# carDoor.net
KiCad netlist of a schematic drawn in Altium Designer
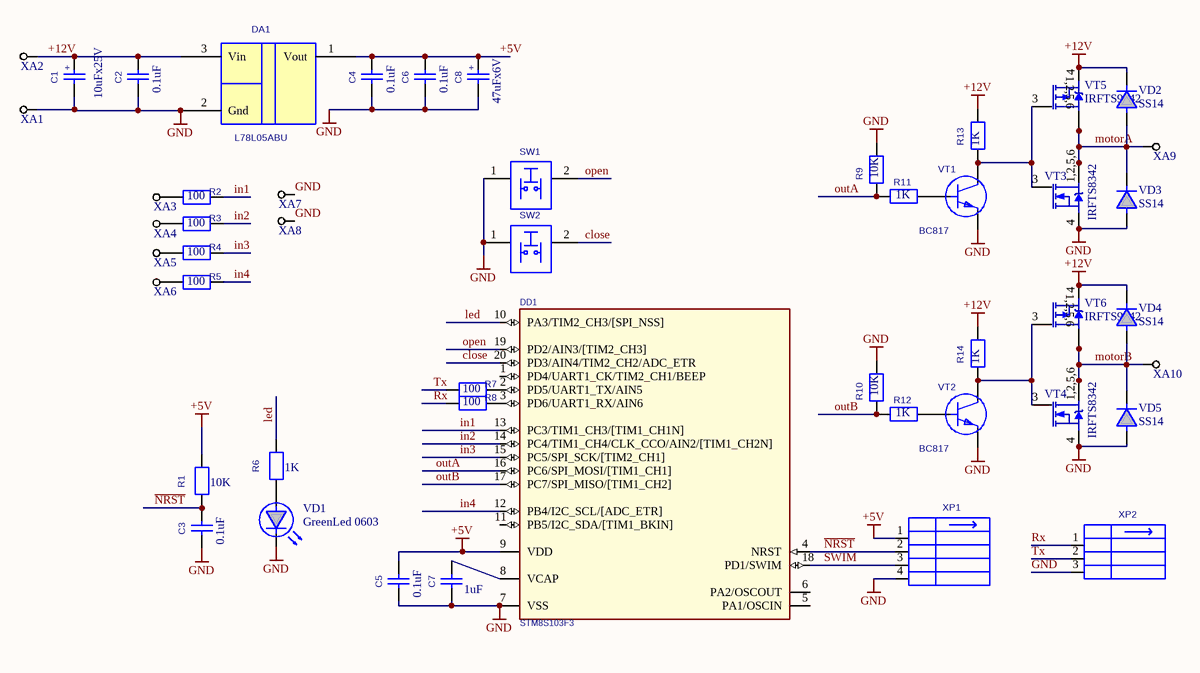
[diagram p0: carDoor.SchDoc]

(export (version "E")
  (design (tool "Eeschema 10.0.6"))
  (components
    (comp (ref "C1")
      (value "10uFx25V")
      (footprint "C-CASE")
      (description "C-CCASE")
      (libsource (lib "Altium-RC") (part "C-CCASE"))
    )
    (comp (ref "C2")
      (value "0.1uF")
      (footprint "C-1608[0603]")
      (description "C-0603")
      (libsource (lib "Altium-RC") (part "C-0603"))
    )
    (comp (ref "C3")
      (value "0.1uF")
      (footprint "C-1608[0603]")
      (description "C-0603")
      (libsource (lib "Altium-RC") (part "C-0603"))
    )
    (comp (ref "C4")
      (value "0.1uF")
      (footprint "C-1608[0603]")
      (description "C-0603")
      (libsource (lib "Altium-RC") (part "C-0603"))
    )
    (comp (ref "C5")
      (value "0.1uF")
      (footprint "C-1608[0603]")
      (description "C-0603")
      (libsource (lib "Altium-RC") (part "C-0603"))
    )
    (comp (ref "C6")
      (value "0.1uF")
      (footprint "C-1608[0603]")
      (description "C-0603")
      (libsource (lib "Altium-RC") (part "C-0603"))
    )
    (comp (ref "C7")
      (value "1uF")
      (footprint "C-1608[0603]")
      (description "C-0603")
      (libsource (lib "Altium-RC") (part "C-0603"))
    )
    (comp (ref "C8")
      (value "47uFx6V")
      (footprint "C-CASE")
      (description "C-CCASE")
      (libsource (lib "Altium-RC") (part "C-CCASE"))
    )
    (comp (ref "DA1")
      (value "L78L05ABU")
      (footprint "SOT89")
      (libsource (lib "Altium-IC") (part "L78L05ABU"))
    )
    (comp (ref "DD1")
      (value "STM8S103F3")
      (footprint "TSSOP20")
      (description "STM8 8-bit microcontroller")
      (libsource (lib "Altium-IC") (part "STM8S103Fx TSSOP20, SO20"))
    )
    (comp (ref "R1")
      (value "10K")
      (footprint "R-1608[0603]")
      (description "R-0603")
      (libsource (lib "Altium-RC") (part "R-0603"))
    )
    (comp (ref "R2")
      (value "100")
      (footprint "R-1608[0603]")
      (description "R-0603")
      (libsource (lib "Altium-RC") (part "R-0603"))
    )
    (comp (ref "R3")
      (value "100")
      (footprint "R-1608[0603]")
      (description "R-0603")
      (libsource (lib "Altium-RC") (part "R-0603"))
    )
    (comp (ref "R4")
      (value "100")
      (footprint "R-1608[0603]")
      (description "R-0603")
      (libsource (lib "Altium-RC") (part "R-0603"))
    )
    (comp (ref "R5")
      (value "100")
      (footprint "R-1608[0603]")
      (description "R-0603")
      (libsource (lib "Altium-RC") (part "R-0603"))
    )
    (comp (ref "R6")
      (value "1K")
      (footprint "R-1608[0603]")
      (description "R-0603")
      (libsource (lib "Altium-RC") (part "R-0603"))
    )
    (comp (ref "R7")
      (value "100")
      (footprint "R-1608[0603]")
      (description "R-0603")
      (libsource (lib "Altium-RC") (part "R-0603"))
    )
    (comp (ref "R8")
      (value "100")
      (footprint "R-1608[0603]")
      (description "R-0603")
      (libsource (lib "Altium-RC") (part "R-0603"))
    )
    (comp (ref "R9")
      (value "10K")
      (footprint "R-1608[0603]")
      (description "R-0603")
      (libsource (lib "Altium-RC") (part "R-0603"))
    )
    (comp (ref "R10")
      (value "10K")
      (footprint "R-1608[0603]")
      (description "R-0603")
      (libsource (lib "Altium-RC") (part "R-0603"))
    )
    (comp (ref "R11")
      (value "1K")
      (footprint "R-1608[0603]")
      (description "R-0603")
      (libsource (lib "Altium-RC") (part "R-0603"))
    )
    (comp (ref "R12")
      (value "1K")
      (footprint "R-1608[0603]")
      (description "R-0603")
      (libsource (lib "Altium-RC") (part "R-0603"))
    )
    (comp (ref "R13")
      (value "1K")
      (footprint "R-1608[0603]")
      (description "R-0603")
      (libsource (lib "Altium-RC") (part "R-0603"))
    )
    (comp (ref "R14")
      (value "1K")
      (footprint "R-1608[0603]")
      (description "R-0603")
      (libsource (lib "Altium-RC") (part "R-0603"))
    )
    (comp (ref "SW1")
      (value "DTSM-32(SWT-10)")
      (footprint "DTSM-32(SWT-10)")
      (libsource (lib "Altium-CONN") (part "DTSM-32(SWT-10)"))
    )
    (comp (ref "SW2")
      (value "DTSM-32(SWT-10)")
      (footprint "DTSM-32(SWT-10)")
      (libsource (lib "Altium-CONN") (part "DTSM-32(SWT-10)"))
    )
    (comp (ref "VD1")
      (value "GreenLed 0603")
      (footprint "LED-0603")
      (description "0603 Green Led")
      (libsource (lib "Altium-OPTO") (part "L-C191KGCT"))
    )
    (comp (ref "VD2")
      (value "SS14")
      (footprint "SMB")
      (description "Surface Mount Schottky Power Rectifier")
      (libsource (lib "Altium-RECT") (part "MBRS140T3G"))
    )
    (comp (ref "VD3")
      (value "SS14")
      (footprint "SMB")
      (description "Surface Mount Schottky Power Rectifier")
      (libsource (lib "") (part "MBRS140T3G_1"))
    )
    (comp (ref "VD4")
      (value "SS14")
      (footprint "SMB")
      (description "Surface Mount Schottky Power Rectifier")
      (libsource (lib "") (part "MBRS140T3G_1"))
    )
    (comp (ref "VD5")
      (value "SS14")
      (footprint "SMB")
      (description "Surface Mount Schottky Power Rectifier")
      (libsource (lib "") (part "MBRS140T3G_1"))
    )
    (comp (ref "VT1") (value "BC817") (footprint "SOT-23") (libsource (lib "Altium-RECT") (part "BC817")))
    (comp (ref "VT2") (value "BC817") (footprint "SOT-23") (libsource (lib "Altium-RECT") (part "BC817")))
    (comp (ref "VT3")
      (value "IRFTS8342")
      (footprint "Micro6")
      (description "HEXFET Power Mosfet N channel")
      (libsource (lib "Altium-RECT") (part "IRFTS8342"))
    )
    (comp (ref "VT4")
      (value "IRFTS8342")
      (footprint "Micro6")
      (description "HEXFET Power Mosfet N channel")
      (libsource (lib "Altium-RECT") (part "IRFTS8342"))
    )
    (comp (ref "VT5")
      (value "IRFTS9342")
      (footprint "Micro6")
      (description "HEXFET Power MOSFET P channel")
      (libsource (lib "Altium-RECT") (part "IRFTS9342"))
    )
    (comp (ref "VT6")
      (value "IRFTS9342")
      (footprint "Micro6")
      (description "HEXFET Power MOSFET P channel")
      (libsource (lib "Altium-RECT") (part "IRFTS9342"))
    )
    (comp (ref "XA1")
      (value "*")
      (footprint "TPad-4x2mm")
      (description "pad for soldering")
      (libsource (lib "Altium-CONN") (part "TPad without via"))
    )
    (comp (ref "XA2")
      (value "*")
      (footprint "TPad-4x2mm")
      (description "pad for soldering")
      (libsource (lib "Altium-CONN") (part "TPad without via"))
    )
    (comp (ref "XA3")
      (value "*")
      (footprint "TPad-3x1.5mm")
      (description "pad for soldering")
      (libsource (lib "Altium-CONN") (part "TPad without via"))
    )
    (comp (ref "XA4")
      (value "*")
      (footprint "TPad-3x1.5mm")
      (description "pad for soldering")
      (libsource (lib "Altium-CONN") (part "TPad without via"))
    )
    (comp (ref "XA5")
      (value "*")
      (footprint "TPad-3x1.5mm")
      (description "pad for soldering")
      (libsource (lib "Altium-CONN") (part "TPad without via"))
    )
    (comp (ref "XA6")
      (value "*")
      (footprint "TPad-3x1.5mm")
      (description "pad for soldering")
      (libsource (lib "Altium-CONN") (part "TPad without via"))
    )
    (comp (ref "XA7")
      (value "*")
      (footprint "TPad-3x1.5mm")
      (description "pad for soldering")
      (libsource (lib "Altium-CONN") (part "TPad without via"))
    )
    (comp (ref "XA8")
      (value "*")
      (footprint "TPad-3x1.5mm")
      (description "pad for soldering")
      (libsource (lib "Altium-CONN") (part "TPad without via"))
    )
    (comp (ref "XA9")
      (value "*")
      (footprint "TPad-4x2mm")
      (description "pad for soldering")
      (libsource (lib "Altium-CONN") (part "TPad without via"))
    )
    (comp (ref "XA10")
      (value "*")
      (footprint "TPad-4x2mm")
      (description "pad for soldering")
      (libsource (lib "Altium-CONN") (part "TPad without via"))
    )
    (comp (ref "XP1") (value "PLS-4") (footprint "PLS4") (libsource (lib "Altium-CONN") (part "PLS-4")))
    (comp (ref "XP2") (value "PLS-3") (footprint "PLS3") (libsource (lib "Altium-CONN") (part "PLS-3")))
  )
  (nets
    (net (code "1") (name "+5V") (class "Default")
      (node (ref "C4") (pin "1") (pintype "passive"))
      (node (ref "C5") (pin "1") (pintype "passive"))
      (node (ref "C6") (pin "1") (pintype "passive"))
      (node (ref "C8") (pin "1") (pinfunction "+_1") (pintype "passive"))
      (node (ref "DA1") (pin "1") (pinfunction "Vout_1") (pintype "passive"))
      (node (ref "DD1") (pin "9") (pinfunction "VDD_9") (pintype "power_in"))
      (node (ref "R1") (pin "2") (pinfunction "2_2") (pintype "passive"))
      (node (ref "XP1") (pin "1") (pintype "passive"))
    )
    (net (code "2") (name "+12V") (class "Default")
      (node (ref "C1") (pin "1") (pinfunction "+_1") (pintype "passive"))
      (node (ref "C2") (pin "1") (pintype "passive"))
      (node (ref "DA1") (pin "3") (pinfunction "Vin_3") (pintype "passive"))
      (node (ref "R13") (pin "2") (pinfunction "2_2") (pintype "passive"))
      (node (ref "R14") (pin "2") (pinfunction "2_2") (pintype "passive"))
      (node (ref "VD2") (pin "1") (pinfunction "K_1") (pintype "passive"))
      (node (ref "VD4") (pin "1") (pinfunction "K_1") (pintype "passive"))
      (node (ref "VT5") (pin "4") (pinfunction "S_4") (pintype "passive"))
      (node (ref "VT6") (pin "4") (pinfunction "S_4") (pintype "passive"))
      (node (ref "XA2") (pin "0") (pinfunction "0_0") (pintype "passive"))
    )
    (net (code "3") (name "/Rx") (class "Default")
      (node (ref "R8") (pin "1") (pinfunction "1_1") (pintype "passive"))
      (node (ref "XP2") (pin "1") (pintype "passive"))
    )
    (net (code "4") (name "/SWIM") (class "Default")
      (node (ref "DD1") (pin "18") (pinfunction "PD1/SWIM_18") (pintype "bidirectional"))
      (node (ref "XP1") (pin "3") (pintype "passive"))
    )
    (net (code "5") (name "/Tx") (class "Default")
      (node (ref "R7") (pin "1") (pinfunction "1_1") (pintype "passive"))
      (node (ref "XP2") (pin "2") (pintype "passive"))
    )
    (net (code "6") (name "/close") (class "Default")
      (node (ref "DD1") (pin "20") (pinfunction "PD3/AIN4/TIM2_CH2/ADC_ETR_20") (pintype "bidirectional"))
      (node (ref "SW2") (pin "2") (pinfunction "pin3_2") (pintype "passive"))
    )
    (net (code "7") (name "/in1") (class "Default")
      (node (ref "DD1") (pin "13") (pinfunction "PC3/TIM1_CH3/[TIM1_CH1N]_13") (pintype "bidirectional"))
      (node (ref "R2") (pin "2") (pinfunction "2_2") (pintype "passive"))
    )
    (net (code "8") (name "/in2") (class "Default")
      (node (ref "DD1") (pin "14") (pinfunction "PC4/TIM1_CH4/CLK_CCO/AIN2/[TIM1_CH2N]_14") (pintype "bidirectional"))
      (node (ref "R3") (pin "2") (pinfunction "2_2") (pintype "passive"))
    )
    (net (code "9") (name "/in3") (class "Default")
      (node (ref "DD1") (pin "15") (pinfunction "PC5/SPI_SCK/[TIM2_CH1]_15") (pintype "bidirectional"))
      (node (ref "R4") (pin "2") (pinfunction "2_2") (pintype "passive"))
    )
    (net (code "10") (name "/in4") (class "Default")
      (node (ref "DD1") (pin "12") (pinfunction "PB4/I2C_SCL/[ADC_ETR]_12") (pintype "bidirectional"))
      (node (ref "R5") (pin "2") (pinfunction "2_2") (pintype "passive"))
    )
    (net (code "11") (name "/led") (class "Default")
      (node (ref "DD1") (pin "10") (pinfunction "PA3/TIM2_CH3/[SPI_NSS]_10") (pintype "bidirectional"))
      (node (ref "R6") (pin "2") (pinfunction "2_2") (pintype "passive"))
    )
    (net (code "12") (name "/motorA") (class "Default")
      (node (ref "VD2") (pin "2") (pinfunction "A_2") (pintype "passive"))
      (node (ref "VD3") (pin "1") (pinfunction "K_1") (pintype "passive"))
      (node (ref "VT3") (pin "1") (pinfunction "D_1") (pintype "passive"))
      (node (ref "VT3") (pin "2") (pinfunction "D_2") (pintype "passive"))
      (node (ref "VT3") (pin "5") (pinfunction "D_5") (pintype "passive"))
      (node (ref "VT3") (pin "6") (pinfunction "D_6") (pintype "passive"))
      (node (ref "VT5") (pin "1") (pinfunction "D_1") (pintype "passive"))
      (node (ref "VT5") (pin "2") (pinfunction "D_2") (pintype "passive"))
      (node (ref "VT5") (pin "5") (pinfunction "D_5") (pintype "passive"))
      (node (ref "VT5") (pin "6") (pinfunction "D_6") (pintype "passive"))
      (node (ref "XA9") (pin "0") (pinfunction "0_0") (pintype "passive"))
    )
    (net (code "13") (name "/motorB") (class "Default")
      (node (ref "VD4") (pin "2") (pinfunction "A_2") (pintype "passive"))
      (node (ref "VD5") (pin "1") (pinfunction "K_1") (pintype "passive"))
      (node (ref "VT4") (pin "1") (pinfunction "D_1") (pintype "passive"))
      (node (ref "VT4") (pin "2") (pinfunction "D_2") (pintype "passive"))
      (node (ref "VT4") (pin "5") (pinfunction "D_5") (pintype "passive"))
      (node (ref "VT4") (pin "6") (pinfunction "D_6") (pintype "passive"))
      (node (ref "VT6") (pin "1") (pinfunction "D_1") (pintype "passive"))
      (node (ref "VT6") (pin "2") (pinfunction "D_2") (pintype "passive"))
      (node (ref "VT6") (pin "5") (pinfunction "D_5") (pintype "passive"))
      (node (ref "VT6") (pin "6") (pinfunction "D_6") (pintype "passive"))
      (node (ref "XA10") (pin "0") (pinfunction "0_0") (pintype "passive"))
    )
    (net (code "14") (name "/open") (class "Default")
      (node (ref "DD1") (pin "19") (pinfunction "PD2/AIN3/[TIM2_CH3]_19") (pintype "bidirectional"))
      (node (ref "SW1") (pin "2") (pinfunction "pin3_2") (pintype "passive"))
    )
    (net (code "15") (name "/outA") (class "Default")
      (node (ref "DD1") (pin "16") (pinfunction "PC6/SPI_MOSI/[TIM1_CH1]_16") (pintype "bidirectional"))
      (node (ref "R11") (pin "1") (pinfunction "1_1") (pintype "passive"))
      (node (ref "R9") (pin "1") (pinfunction "1_1") (pintype "passive"))
    )
    (net (code "16") (name "/outB") (class "Default")
      (node (ref "DD1") (pin "17") (pinfunction "PC7/SPI_MISO/[TIM1_CH2]_17") (pintype "bidirectional"))
      (node (ref "R10") (pin "1") (pinfunction "1_1") (pintype "passive"))
      (node (ref "R12") (pin "1") (pinfunction "1_1") (pintype "passive"))
    )
    (net (code "17") (name "/~{NRST}") (class "Default")
      (node (ref "C3") (pin "1") (pintype "passive"))
      (node (ref "DD1") (pin "4") (pinfunction "NRST_4") (pintype "input"))
      (node (ref "R1") (pin "1") (pinfunction "1_1") (pintype "passive"))
      (node (ref "XP1") (pin "2") (pintype "passive"))
    )
    (net (code "18") (name "GND") (class "Default")
      (node (ref "C1") (pin "2") (pinfunction "-_2") (pintype "passive"))
      (node (ref "C2") (pin "2") (pintype "passive"))
      (node (ref "C3") (pin "2") (pintype "passive"))
      (node (ref "C4") (pin "2") (pintype "passive"))
      (node (ref "C5") (pin "2") (pintype "passive"))
      (node (ref "C6") (pin "2") (pintype "passive"))
      (node (ref "C7") (pin "2") (pintype "passive"))
      (node (ref "C8") (pin "2") (pinfunction "-_2") (pintype "passive"))
      (node (ref "DA1") (pin "2") (pinfunction "Gnd_2") (pintype "passive"))
      (node (ref "DD1") (pin "7") (pinfunction "VSS_7") (pintype "power_in"))
      (node (ref "R10") (pin "2") (pinfunction "2_2") (pintype "passive"))
      (node (ref "R9") (pin "2") (pinfunction "2_2") (pintype "passive"))
      (node (ref "SW1") (pin "1") (pinfunction "pin1_1") (pintype "passive"))
      (node (ref "SW2") (pin "1") (pinfunction "pin1_1") (pintype "passive"))
      (node (ref "VD1") (pin "1") (pinfunction "K_1") (pintype "passive"))
      (node (ref "VD3") (pin "2") (pinfunction "A_2") (pintype "passive"))
      (node (ref "VD5") (pin "2") (pinfunction "A_2") (pintype "passive"))
      (node (ref "VT1") (pin "2") (pinfunction "E_2") (pintype "passive"))
      (node (ref "VT2") (pin "2") (pinfunction "E_2") (pintype "passive"))
      (node (ref "VT3") (pin "4") (pinfunction "S_4") (pintype "passive"))
      (node (ref "VT4") (pin "4") (pinfunction "S_4") (pintype "passive"))
      (node (ref "XA1") (pin "0") (pinfunction "0_0") (pintype "passive"))
      (node (ref "XA7") (pin "0") (pinfunction "0_0") (pintype "passive"))
      (node (ref "XA8") (pin "0") (pinfunction "0_0") (pintype "passive"))
      (node (ref "XP1") (pin "4") (pintype "passive"))
      (node (ref "XP2") (pin "3") (pintype "passive"))
    )
    (net (code "19") (name "Net-(DD1-PD5{slash}UART1_TX{slash}AIN5)") (class "Default")
      (node (ref "DD1") (pin "2") (pinfunction "PD5/UART1_TX/AIN5_2") (pintype "bidirectional"))
      (node (ref "R7") (pin "2") (pinfunction "2_2") (pintype "passive"))
    )
    (net (code "20") (name "Net-(DD1-PD6{slash}UART1_RX{slash}AIN6)") (class "Default")
      (node (ref "DD1") (pin "3") (pinfunction "PD6/UART1_RX/AIN6_3") (pintype "bidirectional"))
      (node (ref "R8") (pin "2") (pinfunction "2_2") (pintype "passive"))
    )
    (net (code "21") (name "Net-(DD1-VCAP)") (class "Default")
      (node (ref "C7") (pin "1") (pintype "passive"))
      (node (ref "DD1") (pin "8") (pinfunction "VCAP_8") (pintype "passive"))
    )
    (net (code "22") (name "Net-(R2-Pad1)") (class "Default")
      (node (ref "R2") (pin "1") (pinfunction "1_1") (pintype "passive"))
      (node (ref "XA3") (pin "0") (pinfunction "0_0") (pintype "passive"))
    )
    (net (code "23") (name "Net-(R3-Pad1)") (class "Default")
      (node (ref "R3") (pin "1") (pinfunction "1_1") (pintype "passive"))
      (node (ref "XA4") (pin "0") (pinfunction "0_0") (pintype "passive"))
    )
    (net (code "24") (name "Net-(R4-Pad1)") (class "Default")
      (node (ref "R4") (pin "1") (pinfunction "1_1") (pintype "passive"))
      (node (ref "XA5") (pin "0") (pinfunction "0_0") (pintype "passive"))
    )
    (net (code "25") (name "Net-(R5-Pad1)") (class "Default")
      (node (ref "R5") (pin "1") (pinfunction "1_1") (pintype "passive"))
      (node (ref "XA6") (pin "0") (pinfunction "0_0") (pintype "passive"))
    )
    (net (code "26") (name "Net-(VD1-A)") (class "Default")
      (node (ref "R6") (pin "1") (pinfunction "1_1") (pintype "passive"))
      (node (ref "VD1") (pin "2") (pinfunction "A_2") (pintype "passive"))
    )
    (net (code "27") (name "Net-(VT1-B)") (class "Default")
      (node (ref "R11") (pin "2") (pinfunction "2_2") (pintype "passive"))
      (node (ref "VT1") (pin "1") (pinfunction "B_1") (pintype "passive"))
    )
    (net (code "28") (name "Net-(VT1-C)") (class "Default")
      (node (ref "R13") (pin "1") (pinfunction "1_1") (pintype "passive"))
      (node (ref "VT1") (pin "3") (pinfunction "C_3") (pintype "passive"))
      (node (ref "VT3") (pin "3") (pinfunction "G_3") (pintype "passive"))
      (node (ref "VT5") (pin "3") (pinfunction "G_3") (pintype "passive"))
    )
    (net (code "29") (name "Net-(VT2-B)") (class "Default")
      (node (ref "R12") (pin "2") (pinfunction "2_2") (pintype "passive"))
      (node (ref "VT2") (pin "1") (pinfunction "B_1") (pintype "passive"))
    )
    (net (code "30") (name "Net-(VT2-C)") (class "Default")
      (node (ref "R14") (pin "1") (pinfunction "1_1") (pintype "passive"))
      (node (ref "VT2") (pin "3") (pinfunction "C_3") (pintype "passive"))
      (node (ref "VT4") (pin "3") (pinfunction "G_3") (pintype "passive"))
      (node (ref "VT6") (pin "3") (pinfunction "G_3") (pintype "passive"))
    )
    (net (code "31") (name "unconnected-(DD1-PA1{slash}OSCIN-Pad5)") (class "Default")
      (node (ref "DD1") (pin "5") (pinfunction "PA1/OSCIN_5") (pintype "passive"))
    )
    (net (code "32") (name "unconnected-(DD1-PA2{slash}OSCOUT-Pad6)") (class "Default")
      (node (ref "DD1") (pin "6") (pinfunction "PA2/OSCOUT_6") (pintype "passive"))
    )
    (net (code "33") (name "unconnected-(DD1-PB5{slash}I2C_SDA{slash}[TIM1_BKIN]-Pad11)") (class "Default")
      (node (ref "DD1") (pin "11") (pinfunction "PB5/I2C_SDA/[TIM1_BKIN]_11") (pintype "bidirectional"))
    )
    (net (code "34") (name "unconnected-(DD1-PD4{slash}UART1_CK{slash}TIM2_CH1{slash}BEEP-Pad1)") (class "Default")
      (node (ref "DD1") (pin "1") (pinfunction "PD4/UART1_CK/TIM2_CH1/BEEP_1") (pintype "bidirectional"))
    )
  )
)
